# pca_mosfet_v3.net
KiCad netlist of a schematic drawn in EAGLE
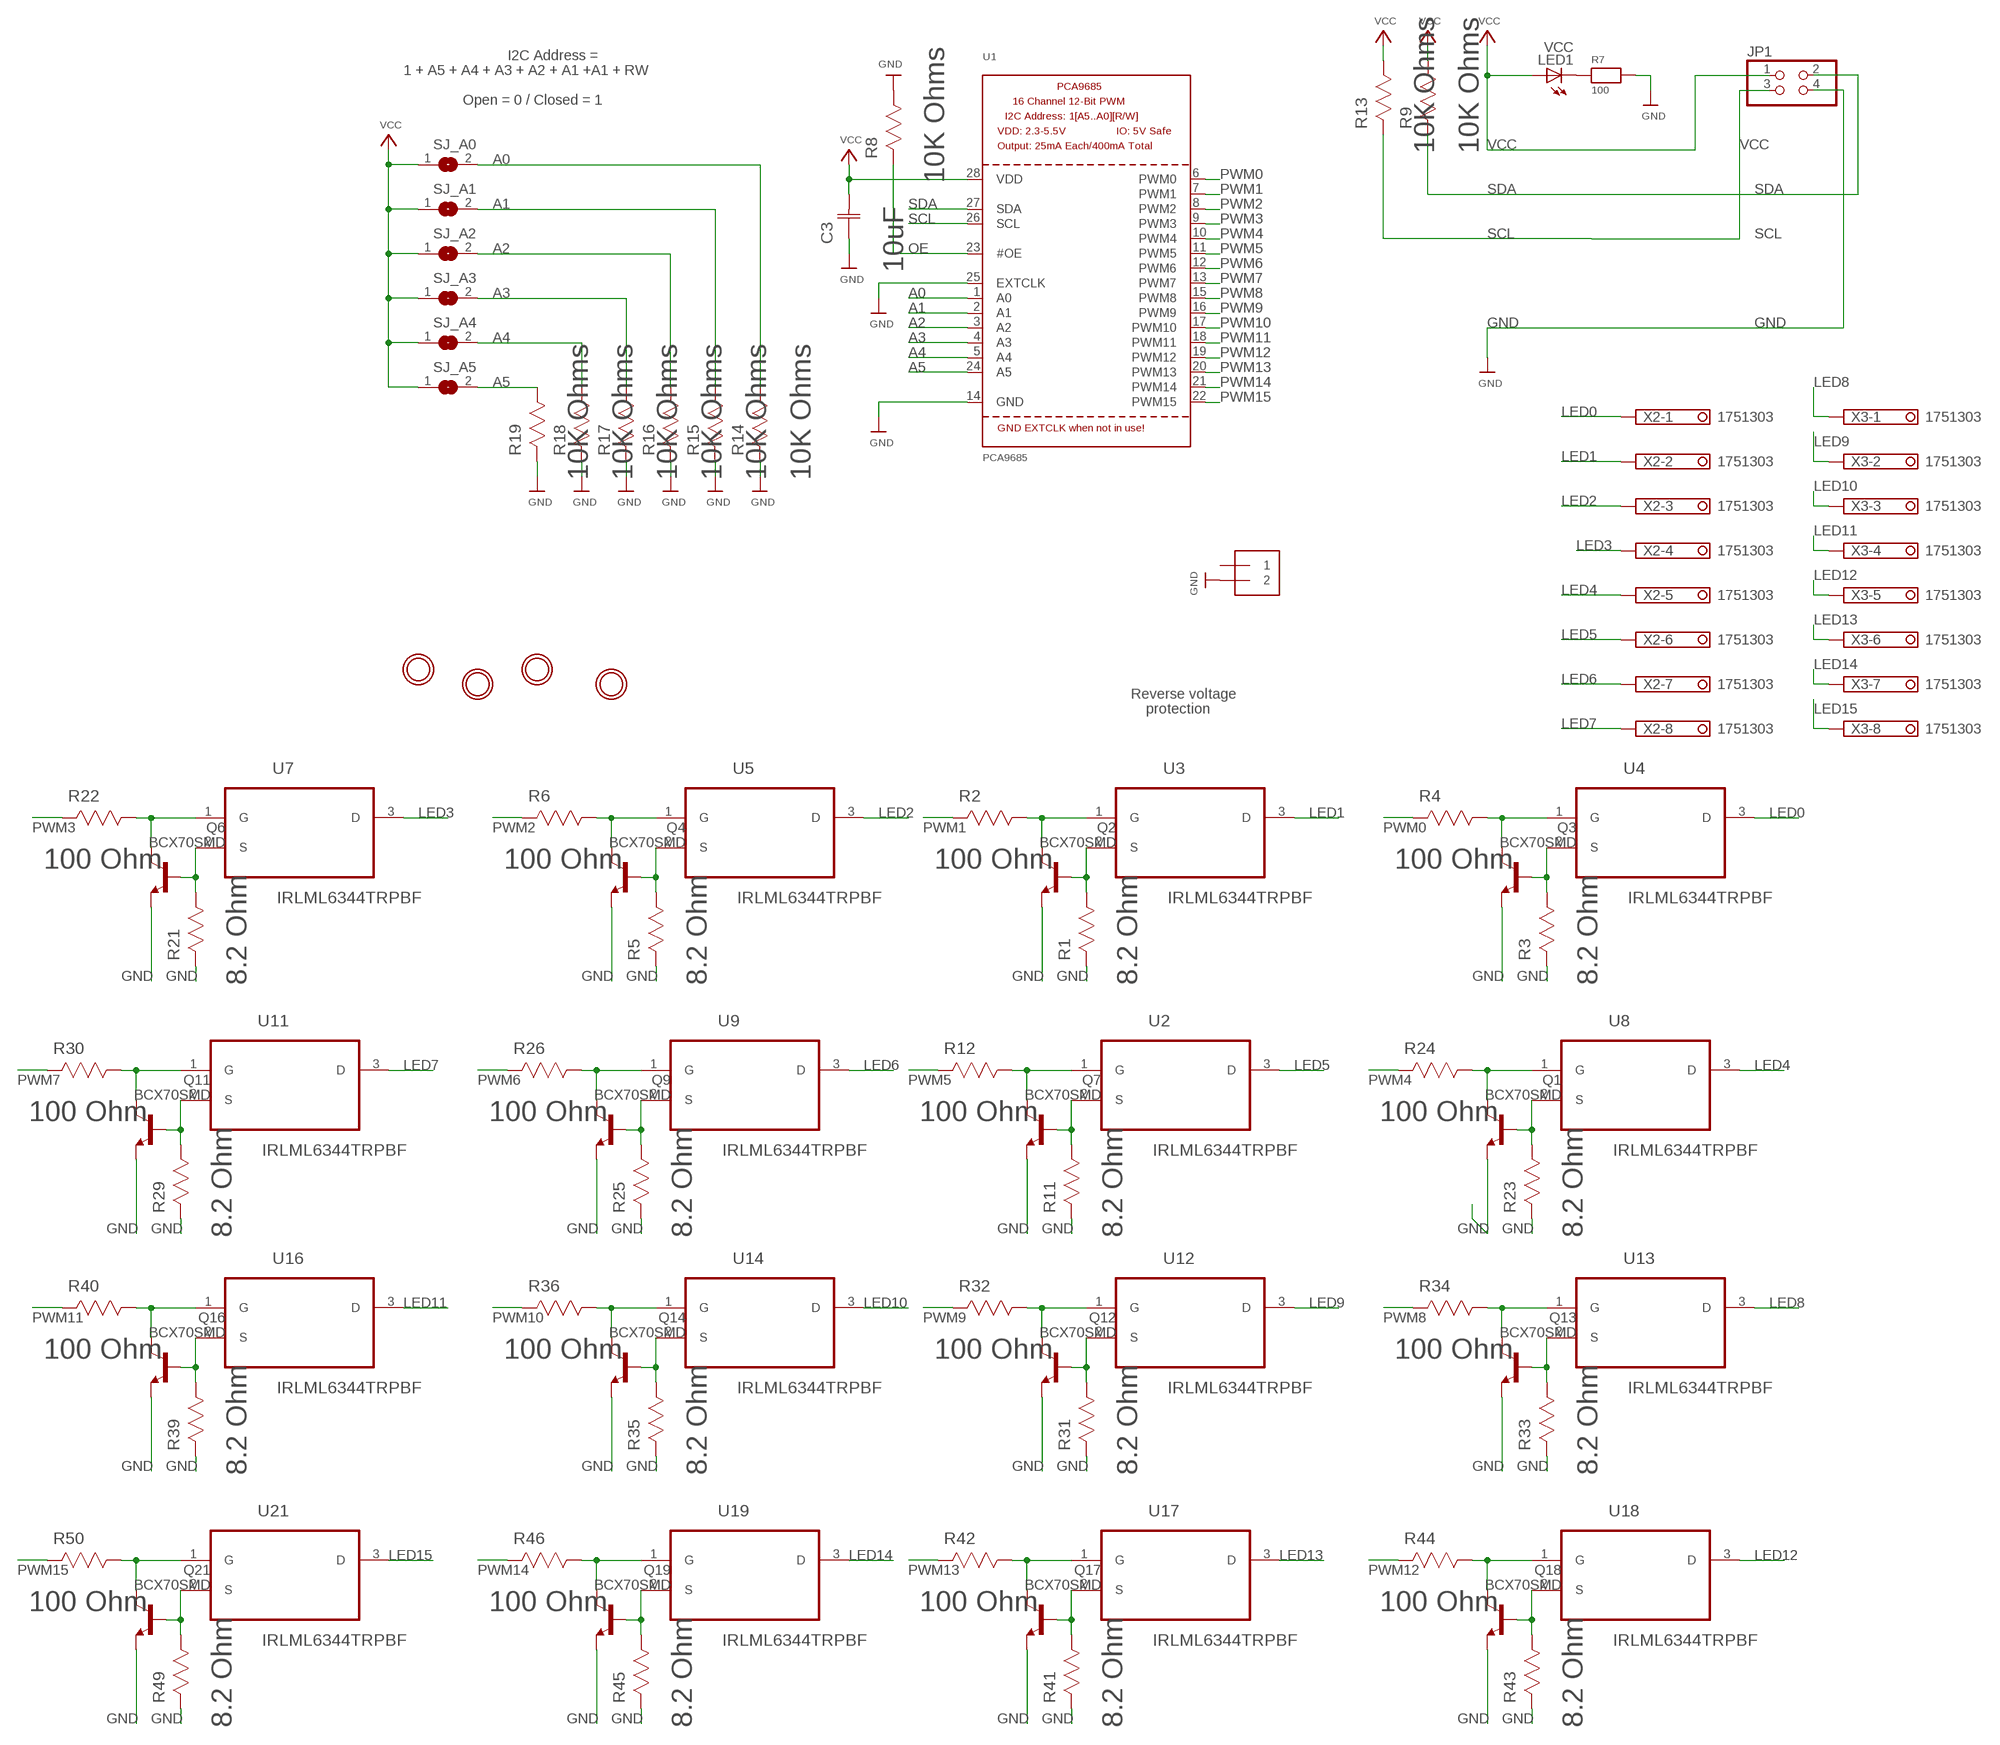
[diagram p0: schematic, sheet 1]

(export (version "E")
  (design (tool "Eeschema 10.0.6"))
  (components
    (comp (ref "C3")
      (value "10uF")
      (footprint "eagle-import:CAPC2013X145N")
      (fields (field (name "MPN") "CC0805KKX5R6BB106") (field (name "TOLERANCE") "±10%"))
      (libsource (lib "eagle-import") (part "CC0805KKX5R6BB106"))
    )
    (comp (ref "J1")
      (value "TERMBLOCK_1X2-3.5MM")
      (footprint "eagle-import:1X2-3.5MM")
      (libsource (lib "eagle-import") (part "TERMBLOCK_1X2-3.5MM"))
    )
    (comp (ref "JP1")
      (value "PINHD-2X02_MICROMATCH")
      (footprint "eagle-import:MICROMATCH-4")
      (libsource (lib "eagle-import") (part "PINHD-2X02_MICROMATCH"))
    )
    (comp (ref "LED1")
      (value "VCC")
      (footprint "eagle-import:SMARTLED-TTW")
      (libsource (lib "eagle-import") (part "LED"))
    )
    (comp (ref "Q1")
      (value "BCX70SMD")
      (footprint "eagle-import:SOT23")
      (libsource (lib "eagle-import") (part "BCX70SMD"))
    )
    (comp (ref "Q2")
      (value "BCX70SMD")
      (footprint "eagle-import:SOT23")
      (libsource (lib "eagle-import") (part "BCX70SMD"))
    )
    (comp (ref "Q3")
      (value "BCX70SMD")
      (footprint "eagle-import:SOT23")
      (libsource (lib "eagle-import") (part "BCX70SMD"))
    )
    (comp (ref "Q4")
      (value "BCX70SMD")
      (footprint "eagle-import:SOT23")
      (libsource (lib "eagle-import") (part "BCX70SMD"))
    )
    (comp (ref "Q6")
      (value "BCX70SMD")
      (footprint "eagle-import:SOT23")
      (libsource (lib "eagle-import") (part "BCX70SMD"))
    )
    (comp (ref "Q7")
      (value "BCX70SMD")
      (footprint "eagle-import:SOT23")
      (libsource (lib "eagle-import") (part "BCX70SMD"))
    )
    (comp (ref "Q9")
      (value "BCX70SMD")
      (footprint "eagle-import:SOT23")
      (libsource (lib "eagle-import") (part "BCX70SMD"))
    )
    (comp (ref "Q11")
      (value "BCX70SMD")
      (footprint "eagle-import:SOT23")
      (libsource (lib "eagle-import") (part "BCX70SMD"))
    )
    (comp (ref "Q12")
      (value "BCX70SMD")
      (footprint "eagle-import:SOT23")
      (libsource (lib "eagle-import") (part "BCX70SMD"))
    )
    (comp (ref "Q13")
      (value "BCX70SMD")
      (footprint "eagle-import:SOT23")
      (libsource (lib "eagle-import") (part "BCX70SMD"))
    )
    (comp (ref "Q14")
      (value "BCX70SMD")
      (footprint "eagle-import:SOT23")
      (libsource (lib "eagle-import") (part "BCX70SMD"))
    )
    (comp (ref "Q16")
      (value "BCX70SMD")
      (footprint "eagle-import:SOT23")
      (libsource (lib "eagle-import") (part "BCX70SMD"))
    )
    (comp (ref "Q17")
      (value "BCX70SMD")
      (footprint "eagle-import:SOT23")
      (libsource (lib "eagle-import") (part "BCX70SMD"))
    )
    (comp (ref "Q18")
      (value "BCX70SMD")
      (footprint "eagle-import:SOT23")
      (libsource (lib "eagle-import") (part "BCX70SMD"))
    )
    (comp (ref "Q19")
      (value "BCX70SMD")
      (footprint "eagle-import:SOT23")
      (libsource (lib "eagle-import") (part "BCX70SMD"))
    )
    (comp (ref "Q21")
      (value "BCX70SMD")
      (footprint "eagle-import:SOT23")
      (libsource (lib "eagle-import") (part "BCX70SMD"))
    )
    (comp (ref "R1")
      (value "8.2 Ohm")
      (footprint "eagle-import:RESC3225X71N")
      (fields (field (name "MPN") "ERJ-P14J8R2U") (field (name "TOLERANCE") "± 1 %"))
      (libsource (lib "eagle-import") (part "ERJ-P14J8R2U"))
    )
    (comp (ref "R2")
      (value "100 Ohm")
      (footprint "eagle-import:RESC3216X71N")
      (fields (field (name "MPN") "RC1206FR-07100RL") (field (name "TOLERANCE") "±1%"))
      (libsource (lib "eagle-import") (part "RC1206FR-07100RL"))
    )
    (comp (ref "R3")
      (value "8.2 Ohm")
      (footprint "eagle-import:RESC3225X71N")
      (fields (field (name "MPN") "ERJ-P14J8R2U") (field (name "TOLERANCE") "± 1 %"))
      (libsource (lib "eagle-import") (part "ERJ-P14J8R2U"))
    )
    (comp (ref "R4")
      (value "100 Ohm")
      (footprint "eagle-import:RESC3216X71N")
      (fields (field (name "MPN") "RC1206FR-07100RL") (field (name "TOLERANCE") "±1%"))
      (libsource (lib "eagle-import") (part "RC1206FR-07100RL"))
    )
    (comp (ref "R5")
      (value "8.2 Ohm")
      (footprint "eagle-import:RESC3225X71N")
      (fields (field (name "MPN") "ERJ-P14J8R2U") (field (name "TOLERANCE") "± 1 %"))
      (libsource (lib "eagle-import") (part "ERJ-P14J8R2U"))
    )
    (comp (ref "R6")
      (value "100 Ohm")
      (footprint "eagle-import:RESC3216X71N")
      (fields (field (name "MPN") "RC1206FR-07100RL") (field (name "TOLERANCE") "±1%"))
      (libsource (lib "eagle-import") (part "RC1206FR-07100RL"))
    )
    (comp (ref "R7")
      (value "100")
      (footprint "eagle-import:1206")
      (libsource (lib "eagle-import") (part "RESISTOR1206"))
    )
    (comp (ref "R8")
      (value "10K Ohms")
      (footprint "eagle-import:RESC3216X71N")
      (fields (field (name "MPN") "RC1206JR-0710KL") (field (name "TOLERANCE") "±5%"))
      (libsource (lib "eagle-import") (part "RC1206JR-0710KL"))
    )
    (comp (ref "R9")
      (value "10K Ohms")
      (footprint "eagle-import:RESC3216X71N")
      (fields (field (name "MPN") "RC1206JR-0710KL") (field (name "TOLERANCE") "±5%"))
      (libsource (lib "eagle-import") (part "RC1206JR-0710KL"))
    )
    (comp (ref "R11")
      (value "8.2 Ohm")
      (footprint "eagle-import:RESC3225X71N")
      (fields (field (name "MPN") "ERJ-P14J8R2U") (field (name "TOLERANCE") "± 1 %"))
      (libsource (lib "eagle-import") (part "ERJ-P14J8R2U"))
    )
    (comp (ref "R12")
      (value "100 Ohm")
      (footprint "eagle-import:RESC3216X71N")
      (fields (field (name "MPN") "RC1206FR-07100RL") (field (name "TOLERANCE") "±1%"))
      (libsource (lib "eagle-import") (part "RC1206FR-07100RL"))
    )
    (comp (ref "R13")
      (value "10K Ohms")
      (footprint "eagle-import:RESC3216X71N")
      (fields (field (name "MPN") "RC1206JR-0710KL") (field (name "TOLERANCE") "±5%"))
      (libsource (lib "eagle-import") (part "RC1206JR-0710KL"))
    )
    (comp (ref "R14")
      (value "10K Ohms")
      (footprint "eagle-import:RESC3216X71N")
      (fields (field (name "MPN") "RC1206JR-0710KL") (field (name "TOLERANCE") "±5%"))
      (libsource (lib "eagle-import") (part "RC1206JR-0710KL"))
    )
    (comp (ref "R15")
      (value "10K Ohms")
      (footprint "eagle-import:RESC3216X71N")
      (fields (field (name "MPN") "RC1206JR-0710KL") (field (name "TOLERANCE") "±5%"))
      (libsource (lib "eagle-import") (part "RC1206JR-0710KL"))
    )
    (comp (ref "R16")
      (value "10K Ohms")
      (footprint "eagle-import:RESC3216X71N")
      (fields (field (name "MPN") "RC1206JR-0710KL") (field (name "TOLERANCE") "±5%"))
      (libsource (lib "eagle-import") (part "RC1206JR-0710KL"))
    )
    (comp (ref "R17")
      (value "10K Ohms")
      (footprint "eagle-import:RESC3216X71N")
      (fields (field (name "MPN") "RC1206JR-0710KL") (field (name "TOLERANCE") "±5%"))
      (libsource (lib "eagle-import") (part "RC1206JR-0710KL"))
    )
    (comp (ref "R18")
      (value "10K Ohms")
      (footprint "eagle-import:RESC3216X71N")
      (fields (field (name "MPN") "RC1206JR-0710KL") (field (name "TOLERANCE") "±5%"))
      (libsource (lib "eagle-import") (part "RC1206JR-0710KL"))
    )
    (comp (ref "R19")
      (value "10K Ohms")
      (footprint "eagle-import:RESC3216X71N")
      (fields (field (name "MPN") "RC1206JR-0710KL") (field (name "TOLERANCE") "±5%"))
      (libsource (lib "eagle-import") (part "RC1206JR-0710KL"))
    )
    (comp (ref "R21")
      (value "8.2 Ohm")
      (footprint "eagle-import:RESC3225X71N")
      (fields (field (name "MPN") "ERJ-P14J8R2U") (field (name "TOLERANCE") "± 1 %"))
      (libsource (lib "eagle-import") (part "ERJ-P14J8R2U"))
    )
    (comp (ref "R22")
      (value "100 Ohm")
      (footprint "eagle-import:RESC3216X71N")
      (fields (field (name "MPN") "RC1206FR-07100RL") (field (name "TOLERANCE") "±1%"))
      (libsource (lib "eagle-import") (part "RC1206FR-07100RL"))
    )
    (comp (ref "R23")
      (value "8.2 Ohm")
      (footprint "eagle-import:RESC3225X71N")
      (fields (field (name "MPN") "ERJ-P14J8R2U") (field (name "TOLERANCE") "± 1 %"))
      (libsource (lib "eagle-import") (part "ERJ-P14J8R2U"))
    )
    (comp (ref "R24")
      (value "100 Ohm")
      (footprint "eagle-import:RESC3216X71N")
      (fields (field (name "MPN") "RC1206FR-07100RL") (field (name "TOLERANCE") "±1%"))
      (libsource (lib "eagle-import") (part "RC1206FR-07100RL"))
    )
    (comp (ref "R25")
      (value "8.2 Ohm")
      (footprint "eagle-import:RESC3225X71N")
      (fields (field (name "MPN") "ERJ-P14J8R2U") (field (name "TOLERANCE") "± 1 %"))
      (libsource (lib "eagle-import") (part "ERJ-P14J8R2U"))
    )
    (comp (ref "R26")
      (value "100 Ohm")
      (footprint "eagle-import:RESC3216X71N")
      (fields (field (name "MPN") "RC1206FR-07100RL") (field (name "TOLERANCE") "±1%"))
      (libsource (lib "eagle-import") (part "RC1206FR-07100RL"))
    )
    (comp (ref "R29")
      (value "8.2 Ohm")
      (footprint "eagle-import:RESC3225X71N")
      (fields (field (name "MPN") "ERJ-P14J8R2U") (field (name "TOLERANCE") "± 1 %"))
      (libsource (lib "eagle-import") (part "ERJ-P14J8R2U"))
    )
    (comp (ref "R30")
      (value "100 Ohm")
      (footprint "eagle-import:RESC3216X71N")
      (fields (field (name "MPN") "RC1206FR-07100RL") (field (name "TOLERANCE") "±1%"))
      (libsource (lib "eagle-import") (part "RC1206FR-07100RL"))
    )
    (comp (ref "R31")
      (value "8.2 Ohm")
      (footprint "eagle-import:RESC3225X71N")
      (fields (field (name "MPN") "ERJ-P14J8R2U") (field (name "TOLERANCE") "± 1 %"))
      (libsource (lib "eagle-import") (part "ERJ-P14J8R2U"))
    )
    (comp (ref "R32")
      (value "100 Ohm")
      (footprint "eagle-import:RESC3216X71N")
      (fields (field (name "MPN") "RC1206FR-07100RL") (field (name "TOLERANCE") "±1%"))
      (libsource (lib "eagle-import") (part "RC1206FR-07100RL"))
    )
    (comp (ref "R33")
      (value "8.2 Ohm")
      (footprint "eagle-import:RESC3225X71N")
      (fields (field (name "MPN") "ERJ-P14J8R2U") (field (name "TOLERANCE") "± 1 %"))
      (libsource (lib "eagle-import") (part "ERJ-P14J8R2U"))
    )
    (comp (ref "R34")
      (value "100 Ohm")
      (footprint "eagle-import:RESC3216X71N")
      (fields (field (name "MPN") "RC1206FR-07100RL") (field (name "TOLERANCE") "±1%"))
      (libsource (lib "eagle-import") (part "RC1206FR-07100RL"))
    )
    (comp (ref "R35")
      (value "8.2 Ohm")
      (footprint "eagle-import:RESC3225X71N")
      (fields (field (name "MPN") "ERJ-P14J8R2U") (field (name "TOLERANCE") "± 1 %"))
      (libsource (lib "eagle-import") (part "ERJ-P14J8R2U"))
    )
    (comp (ref "R36")
      (value "100 Ohm")
      (footprint "eagle-import:RESC3216X71N")
      (fields (field (name "MPN") "RC1206FR-07100RL") (field (name "TOLERANCE") "±1%"))
      (libsource (lib "eagle-import") (part "RC1206FR-07100RL"))
    )
    (comp (ref "R39")
      (value "8.2 Ohm")
      (footprint "eagle-import:RESC3225X71N")
      (fields (field (name "MPN") "ERJ-P14J8R2U") (field (name "TOLERANCE") "± 1 %"))
      (libsource (lib "eagle-import") (part "ERJ-P14J8R2U"))
    )
    (comp (ref "R40")
      (value "100 Ohm")
      (footprint "eagle-import:RESC3216X71N")
      (fields (field (name "MPN") "RC1206FR-07100RL") (field (name "TOLERANCE") "±1%"))
      (libsource (lib "eagle-import") (part "RC1206FR-07100RL"))
    )
    (comp (ref "R41")
      (value "8.2 Ohm")
      (footprint "eagle-import:RESC3225X71N")
      (fields (field (name "MPN") "ERJ-P14J8R2U") (field (name "TOLERANCE") "± 1 %"))
      (libsource (lib "eagle-import") (part "ERJ-P14J8R2U"))
    )
    (comp (ref "R42")
      (value "100 Ohm")
      (footprint "eagle-import:RESC3216X71N")
      (fields (field (name "MPN") "RC1206FR-07100RL") (field (name "TOLERANCE") "±1%"))
      (libsource (lib "eagle-import") (part "RC1206FR-07100RL"))
    )
    (comp (ref "R43")
      (value "8.2 Ohm")
      (footprint "eagle-import:RESC3225X71N")
      (fields (field (name "MPN") "ERJ-P14J8R2U") (field (name "TOLERANCE") "± 1 %"))
      (libsource (lib "eagle-import") (part "ERJ-P14J8R2U"))
    )
    (comp (ref "R44")
      (value "100 Ohm")
      (footprint "eagle-import:RESC3216X71N")
      (fields (field (name "MPN") "RC1206FR-07100RL") (field (name "TOLERANCE") "±1%"))
      (libsource (lib "eagle-import") (part "RC1206FR-07100RL"))
    )
    (comp (ref "R45")
      (value "8.2 Ohm")
      (footprint "eagle-import:RESC3225X71N")
      (fields (field (name "MPN") "ERJ-P14J8R2U") (field (name "TOLERANCE") "± 1 %"))
      (libsource (lib "eagle-import") (part "ERJ-P14J8R2U"))
    )
    (comp (ref "R46")
      (value "100 Ohm")
      (footprint "eagle-import:RESC3216X71N")
      (fields (field (name "MPN") "RC1206FR-07100RL") (field (name "TOLERANCE") "±1%"))
      (libsource (lib "eagle-import") (part "RC1206FR-07100RL"))
    )
    (comp (ref "R49")
      (value "8.2 Ohm")
      (footprint "eagle-import:RESC3225X71N")
      (fields (field (name "MPN") "ERJ-P14J8R2U") (field (name "TOLERANCE") "± 1 %"))
      (libsource (lib "eagle-import") (part "ERJ-P14J8R2U"))
    )
    (comp (ref "R50")
      (value "100 Ohm")
      (footprint "eagle-import:RESC3216X71N")
      (fields (field (name "MPN") "RC1206FR-07100RL") (field (name "TOLERANCE") "±1%"))
      (libsource (lib "eagle-import") (part "RC1206FR-07100RL"))
    )
    (comp (ref "SJ_A0")
      (value "SOLDERJUMPERREFLOW_NOPASTE")
      (footprint "eagle-import:SOLDERJUMPER_REFLOW_NOPASTE")
      (libsource (lib "eagle-import") (part "SOLDERJUMPERREFLOW_NOPASTE"))
    )
    (comp (ref "SJ_A1")
      (value "SOLDERJUMPERREFLOW_NOPASTE")
      (footprint "eagle-import:SOLDERJUMPER_REFLOW_NOPASTE")
      (libsource (lib "eagle-import") (part "SOLDERJUMPERREFLOW_NOPASTE"))
    )
    (comp (ref "SJ_A2")
      (value "SOLDERJUMPERREFLOW_NOPASTE")
      (footprint "eagle-import:SOLDERJUMPER_REFLOW_NOPASTE")
      (libsource (lib "eagle-import") (part "SOLDERJUMPERREFLOW_NOPASTE"))
    )
    (comp (ref "SJ_A3")
      (value "SOLDERJUMPERREFLOW_NOPASTE")
      (footprint "eagle-import:SOLDERJUMPER_REFLOW_NOPASTE")
      (libsource (lib "eagle-import") (part "SOLDERJUMPERREFLOW_NOPASTE"))
    )
    (comp (ref "SJ_A4")
      (value "SOLDERJUMPERREFLOW_NOPASTE")
      (footprint "eagle-import:SOLDERJUMPER_REFLOW_NOPASTE")
      (libsource (lib "eagle-import") (part "SOLDERJUMPERREFLOW_NOPASTE"))
    )
    (comp (ref "SJ_A5")
      (value "SOLDERJUMPERREFLOW_NOPASTE")
      (footprint "eagle-import:SOLDERJUMPER_REFLOW_NOPASTE")
      (libsource (lib "eagle-import") (part "SOLDERJUMPERREFLOW_NOPASTE"))
    )
    (comp (ref "U$1")
      (value "MOUNTINGHOLE2.5")
      (footprint "eagle-import:MOUNTINGHOLE_2.5_PLATED")
      (libsource (lib "eagle-import") (part "MOUNTINGHOLE2.5"))
    )
    (comp (ref "U$2")
      (value "MOUNTINGHOLE2.5")
      (footprint "eagle-import:MOUNTINGHOLE_2.5_PLATED")
      (libsource (lib "eagle-import") (part "MOUNTINGHOLE2.5"))
    )
    (comp (ref "U$3")
      (value "MOUNTINGHOLE2.5")
      (footprint "eagle-import:MOUNTINGHOLE_2.5_PLATED")
      (libsource (lib "eagle-import") (part "MOUNTINGHOLE2.5"))
    )
    (comp (ref "U$48")
      (value "MOUNTINGHOLE2.5")
      (footprint "eagle-import:MOUNTINGHOLE_2.5_PLATED")
      (libsource (lib "eagle-import") (part "MOUNTINGHOLE2.5"))
    )
    (comp (ref "U1")
      (value "PCA9685")
      (footprint "eagle-import:TSSOP28")
      (libsource (lib "eagle-import") (part "PCA9685"))
    )
    (comp (ref "U2")
      (value "IRLML6344TRPBF")
      (footprint "eagle-import:SOT95P240X112-3N")
      (libsource (lib "eagle-import") (part "IRLML6344TRPBF"))
    )
    (comp (ref "U3")
      (value "IRLML6344TRPBF")
      (footprint "eagle-import:SOT95P240X112-3N")
      (libsource (lib "eagle-import") (part "IRLML6344TRPBF"))
    )
    (comp (ref "U4")
      (value "IRLML6344TRPBF")
      (footprint "eagle-import:SOT95P240X112-3N")
      (libsource (lib "eagle-import") (part "IRLML6344TRPBF"))
    )
    (comp (ref "U5")
      (value "IRLML6344TRPBF")
      (footprint "eagle-import:SOT95P240X112-3N")
      (libsource (lib "eagle-import") (part "IRLML6344TRPBF"))
    )
    (comp (ref "U7")
      (value "IRLML6344TRPBF")
      (footprint "eagle-import:SOT95P240X112-3N")
      (libsource (lib "eagle-import") (part "IRLML6344TRPBF"))
    )
    (comp (ref "U8")
      (value "IRLML6344TRPBF")
      (footprint "eagle-import:SOT95P240X112-3N")
      (libsource (lib "eagle-import") (part "IRLML6344TRPBF"))
    )
    (comp (ref "U9")
      (value "IRLML6344TRPBF")
      (footprint "eagle-import:SOT95P240X112-3N")
      (libsource (lib "eagle-import") (part "IRLML6344TRPBF"))
    )
    (comp (ref "U11")
      (value "IRLML6344TRPBF")
      (footprint "eagle-import:SOT95P240X112-3N")
      (libsource (lib "eagle-import") (part "IRLML6344TRPBF"))
    )
    (comp (ref "U12")
      (value "IRLML6344TRPBF")
      (footprint "eagle-import:SOT95P240X112-3N")
      (libsource (lib "eagle-import") (part "IRLML6344TRPBF"))
    )
    (comp (ref "U13")
      (value "IRLML6344TRPBF")
      (footprint "eagle-import:SOT95P240X112-3N")
      (libsource (lib "eagle-import") (part "IRLML6344TRPBF"))
    )
    (comp (ref "U14")
      (value "IRLML6344TRPBF")
      (footprint "eagle-import:SOT95P240X112-3N")
      (libsource (lib "eagle-import") (part "IRLML6344TRPBF"))
    )
    (comp (ref "U16")
      (value "IRLML6344TRPBF")
      (footprint "eagle-import:SOT95P240X112-3N")
      (libsource (lib "eagle-import") (part "IRLML6344TRPBF"))
    )
    (comp (ref "U17")
      (value "IRLML6344TRPBF")
      (footprint "eagle-import:SOT95P240X112-3N")
      (libsource (lib "eagle-import") (part "IRLML6344TRPBF"))
    )
    (comp (ref "U18")
      (value "IRLML6344TRPBF")
      (footprint "eagle-import:SOT95P240X112-3N")
      (libsource (lib "eagle-import") (part "IRLML6344TRPBF"))
    )
    (comp (ref "U19")
      (value "IRLML6344TRPBF")
      (footprint "eagle-import:SOT95P240X112-3N")
      (libsource (lib "eagle-import") (part "IRLML6344TRPBF"))
    )
    (comp (ref "U21")
      (value "IRLML6344TRPBF")
      (footprint "eagle-import:SOT95P240X112-3N")
      (libsource (lib "eagle-import") (part "IRLML6344TRPBF"))
    )
    (comp (ref "X2")
      (value "1751303")
      (footprint "eagle-import:1751303")
      (libsource (lib "eagle-import") (part "1751303"))
    )
    (comp (ref "X3")
      (value "1751303")
      (footprint "eagle-import:1751303")
      (libsource (lib "eagle-import") (part "1751303"))
    )
  )
  (nets
    (net (code "1") (name "/A0") (class "Default")
      (node (ref "R14") (pin "1") (pinfunction "R1_1") (pintype "passive"))
      (node (ref "SJ_A0") (pin "2") (pinfunction "2_2") (pintype "passive"))
      (node (ref "U1") (pin "1") (pinfunction "A0_1") (pintype "bidirectional"))
    )
    (net (code "2") (name "/A1") (class "Default")
      (node (ref "R15") (pin "1") (pinfunction "R1_1") (pintype "passive"))
      (node (ref "SJ_A1") (pin "2") (pinfunction "2_2") (pintype "passive"))
      (node (ref "U1") (pin "2") (pinfunction "A1_2") (pintype "bidirectional"))
    )
    (net (code "3") (name "/A2") (class "Default")
      (node (ref "R16") (pin "1") (pinfunction "R1_1") (pintype "passive"))
      (node (ref "SJ_A2") (pin "2") (pinfunction "2_2") (pintype "passive"))
      (node (ref "U1") (pin "3") (pinfunction "A2_3") (pintype "bidirectional"))
    )
    (net (code "4") (name "/A3") (class "Default")
      (node (ref "R17") (pin "1") (pinfunction "R1_1") (pintype "passive"))
      (node (ref "SJ_A3") (pin "2") (pinfunction "2_2") (pintype "passive"))
      (node (ref "U1") (pin "4") (pinfunction "A3_4") (pintype "bidirectional"))
    )
    (net (code "5") (name "/A4") (class "Default")
      (node (ref "R18") (pin "1") (pinfunction "R1_1") (pintype "passive"))
      (node (ref "SJ_A4") (pin "2") (pinfunction "2_2") (pintype "passive"))
      (node (ref "U1") (pin "5") (pinfunction "A4_5") (pintype "bidirectional"))
    )
    (net (code "6") (name "/A5") (class "Default")
      (node (ref "R19") (pin "1") (pinfunction "R1_1") (pintype "passive"))
      (node (ref "SJ_A5") (pin "2") (pinfunction "2_2") (pintype "passive"))
      (node (ref "U1") (pin "24") (pinfunction "A5_24") (pintype "bidirectional"))
    )
    (net (code "7") (name "/LED0") (class "Default")
      (node (ref "U4") (pin "3") (pinfunction "D_3") (pintype "output"))
      (node (ref "X2") (pin "1") (pinfunction "K_1") (pintype "passive"))
    )
    (net (code "8") (name "/LED1") (class "Default")
      (node (ref "U3") (pin "3") (pinfunction "D_3") (pintype "output"))
      (node (ref "X2") (pin "2") (pinfunction "K_2") (pintype "passive"))
    )
    (net (code "9") (name "/LED2") (class "Default")
      (node (ref "U5") (pin "3") (pinfunction "D_3") (pintype "output"))
      (node (ref "X2") (pin "3") (pinfunction "K_3") (pintype "passive"))
    )
    (net (code "10") (name "/LED3") (class "Default")
      (node (ref "U7") (pin "3") (pinfunction "D_3") (pintype "output"))
      (node (ref "X2") (pin "4") (pinfunction "K_4") (pintype "passive"))
    )
    (net (code "11") (name "/LED4") (class "Default")
      (node (ref "U8") (pin "3") (pinfunction "D_3") (pintype "output"))
      (node (ref "X2") (pin "5") (pinfunction "K_5") (pintype "passive"))
    )
    (net (code "12") (name "/LED5") (class "Default")
      (node (ref "U2") (pin "3") (pinfunction "D_3") (pintype "output"))
      (node (ref "X2") (pin "6") (pinfunction "K_6") (pintype "passive"))
    )
    (net (code "13") (name "/LED6") (class "Default")
      (node (ref "U9") (pin "3") (pinfunction "D_3") (pintype "output"))
      (node (ref "X2") (pin "7") (pinfunction "K_7") (pintype "passive"))
    )
    (net (code "14") (name "/LED7") (class "Default")
      (node (ref "U11") (pin "3") (pinfunction "D_3") (pintype "output"))
      (node (ref "X2") (pin "8") (pinfunction "K_8") (pintype "passive"))
    )
    (net (code "15") (name "/LED8") (class "Default")
      (node (ref "U13") (pin "3") (pinfunction "D_3") (pintype "output"))
      (node (ref "X3") (pin "1") (pinfunction "K_1") (pintype "passive"))
    )
    (net (code "16") (name "/LED9") (class "Default")
      (node (ref "U12") (pin "3") (pinfunction "D_3") (pintype "output"))
      (node (ref "X3") (pin "2") (pinfunction "K_2") (pintype "passive"))
    )
    (net (code "17") (name "/LED10") (class "Default")
      (node (ref "U14") (pin "3") (pinfunction "D_3") (pintype "output"))
      (node (ref "X3") (pin "3") (pinfunction "K_3") (pintype "passive"))
    )
    (net (code "18") (name "/LED11") (class "Default")
      (node (ref "U16") (pin "3") (pinfunction "D_3") (pintype "output"))
      (node (ref "X3") (pin "4") (pinfunction "K_4") (pintype "passive"))
    )
    (net (code "19") (name "/LED12") (class "Default")
      (node (ref "U18") (pin "3") (pinfunction "D_3") (pintype "output"))
      (node (ref "X3") (pin "5") (pinfunction "K_5") (pintype "passive"))
    )
    (net (code "20") (name "/LED13") (class "Default")
      (node (ref "U17") (pin "3") (pinfunction "D_3") (pintype "output"))
      (node (ref "X3") (pin "6") (pinfunction "K_6") (pintype "passive"))
    )
    (net (code "21") (name "/LED14") (class "Default")
      (node (ref "U19") (pin "3") (pinfunction "D_3") (pintype "output"))
      (node (ref "X3") (pin "7") (pinfunction "K_7") (pintype "passive"))
    )
    (net (code "22") (name "/LED15") (class "Default")
      (node (ref "U21") (pin "3") (pinfunction "D_3") (pintype "output"))
      (node (ref "X3") (pin "8") (pinfunction "K_8") (pintype "passive"))
    )
    (net (code "23") (name "/OE") (class "Default")
      (node (ref "R8") (pin "2") (pinfunction "R2_2") (pintype "passive"))
      (node (ref "U1") (pin "23") (pinfunction "#OE_23") (pintype "input"))
    )
    (net (code "24") (name "/PWM0") (class "Default")
      (node (ref "R4") (pin "2") (pinfunction "R2_2") (pintype "passive"))
      (node (ref "U1") (pin "6") (pinfunction "PWM0_6") (pintype "output"))
    )
    (net (code "25") (name "/PWM1") (class "Default")
      (node (ref "R2") (pin "2") (pinfunction "R2_2") (pintype "passive"))
      (node (ref "U1") (pin "7") (pinfunction "PWM1_7") (pintype "output"))
    )
    (net (code "26") (name "/PWM2") (class "Default")
      (node (ref "R6") (pin "2") (pinfunction "R2_2") (pintype "passive"))
      (node (ref "U1") (pin "8") (pinfunction "PWM2_8") (pintype "output"))
    )
    (net (code "27") (name "/PWM3") (class "Default")
      (node (ref "R22") (pin "2") (pinfunction "R2_2") (pintype "passive"))
      (node (ref "U1") (pin "9") (pinfunction "PWM3_9") (pintype "output"))
    )
    (net (code "28") (name "/PWM4") (class "Default")
      (node (ref "R24") (pin "2") (pinfunction "R2_2") (pintype "passive"))
      (node (ref "U1") (pin "10") (pinfunction "PWM4_10") (pintype "output"))
    )
    (net (code "29") (name "/PWM5") (class "Default")
      (node (ref "R12") (pin "2") (pinfunction "R2_2") (pintype "passive"))
      (node (ref "U1") (pin "11") (pinfunction "PWM5_11") (pintype "output"))
    )
    (net (code "30") (name "/PWM6") (class "Default")
      (node (ref "R26") (pin "2") (pinfunction "R2_2") (pintype "passive"))
      (node (ref "U1") (pin "12") (pinfunction "PWM6_12") (pintype "output"))
    )
    (net (code "31") (name "/PWM7") (class "Default")
      (node (ref "R30") (pin "2") (pinfunction "R2_2") (pintype "passive"))
      (node (ref "U1") (pin "13") (pinfunction "PWM7_13") (pintype "output"))
    )
    (net (code "32") (name "/PWM8") (class "Default")
      (node (ref "R34") (pin "2") (pinfunction "R2_2") (pintype "passive"))
      (node (ref "U1") (pin "15") (pinfunction "PWM8_15") (pintype "output"))
    )
    (net (code "33") (name "/PWM9") (class "Default")
      (node (ref "R32") (pin "2") (pinfunction "R2_2") (pintype "passive"))
      (node (ref "U1") (pin "16") (pinfunction "PWM9_16") (pintype "output"))
    )
    (net (code "34") (name "/PWM10") (class "Default")
      (node (ref "R36") (pin "2") (pinfunction "R2_2") (pintype "passive"))
      (node (ref "U1") (pin "17") (pinfunction "PWM10_17") (pintype "output"))
    )
    (net (code "35") (name "/PWM11") (class "Default")
      (node (ref "R40") (pin "2") (pinfunction "R2_2") (pintype "passive"))
      (node (ref "U1") (pin "18") (pinfunction "PWM11_18") (pintype "output"))
    )
    (net (code "36") (name "/PWM12") (class "Default")
      (node (ref "R44") (pin "2") (pinfunction "R2_2") (pintype "passive"))
      (node (ref "U1") (pin "19") (pinfunction "PWM12_19") (pintype "output"))
    )
    (net (code "37") (name "/PWM13") (class "Default")
      (node (ref "R42") (pin "2") (pinfunction "R2_2") (pintype "passive"))
      (node (ref "U1") (pin "20") (pinfunction "PWM13_20") (pintype "output"))
    )
    (net (code "38") (name "/PWM14") (class "Default")
      (node (ref "R46") (pin "2") (pinfunction "R2_2") (pintype "passive"))
      (node (ref "U1") (pin "21") (pinfunction "PWM14_21") (pintype "output"))
    )
    (net (code "39") (name "/PWM15") (class "Default")
      (node (ref "R50") (pin "2") (pinfunction "R2_2") (pintype "passive"))
      (node (ref "U1") (pin "22") (pinfunction "PWM15_22") (pintype "output"))
    )
    (net (code "40") (name "/SCL") (class "Default")
      (node (ref "JP1") (pin "3") (pinfunction "3_3") (pintype "passive"))
      (node (ref "R13") (pin "2") (pinfunction "R2_2") (pintype "passive"))
      (node (ref "U1") (pin "26") (pinfunction "SCL_26") (pintype "bidirectional"))
    )
    (net (code "41") (name "/SDA") (class "Default")
      (node (ref "JP1") (pin "2") (pinfunction "2_2") (pintype "passive"))
      (node (ref "R9") (pin "2") (pinfunction "R2_2") (pintype "passive"))
      (node (ref "U1") (pin "27") (pinfunction "SDA_27") (pintype "bidirectional"))
    )
    (net (code "42") (name "GND") (class "Default")
      (node (ref "C3") (pin "1") (pinfunction "C1_1") (pintype "passive"))
      (node (ref "J1") (pin "2") (pinfunction "2_2") (pintype "passive"))
      (node (ref "JP1") (pin "4") (pinfunction "4_4") (pintype "passive"))
      (node (ref "Q1") (pin "2") (pinfunction "E_2") (pintype "passive"))
      (node (ref "Q11") (pin "2") (pinfunction "E_2") (pintype "passive"))
      (node (ref "Q12") (pin "2") (pinfunction "E_2") (pintype "passive"))
      (node (ref "Q13") (pin "2") (pinfunction "E_2") (pintype "passive"))
      (node (ref "Q14") (pin "2") (pinfunction "E_2") (pintype "passive"))
      (node (ref "Q16") (pin "2") (pinfunction "E_2") (pintype "passive"))
      (node (ref "Q17") (pin "2") (pinfunction "E_2") (pintype "passive"))
      (node (ref "Q18") (pin "2") (pinfunction "E_2") (pintype "passive"))
      (node (ref "Q19") (pin "2") (pinfunction "E_2") (pintype "passive"))
      (node (ref "Q2") (pin "2") (pinfunction "E_2") (pintype "passive"))
      (node (ref "Q21") (pin "2") (pinfunction "E_2") (pintype "passive"))
      (node (ref "Q3") (pin "2") (pinfunction "E_2") (pintype "passive"))
      (node (ref "Q4") (pin "2") (pinfunction "E_2") (pintype "passive"))
      (node (ref "Q6") (pin "2") (pinfunction "E_2") (pintype "passive"))
      (node (ref "Q7") (pin "2") (pinfunction "E_2") (pintype "passive"))
      (node (ref "Q9") (pin "2") (pinfunction "E_2") (pintype "passive"))
      (node (ref "R1") (pin "2") (pinfunction "R2_2") (pintype "passive"))
      (node (ref "R11") (pin "2") (pinfunction "R2_2") (pintype "passive"))
      (node (ref "R14") (pin "2") (pinfunction "R2_2") (pintype "passive"))
      (node (ref "R15") (pin "2") (pinfunction "R2_2") (pintype "passive"))
      (node (ref "R16") (pin "2") (pinfunction "R2_2") (pintype "passive"))
      (node (ref "R17") (pin "2") (pinfunction "R2_2") (pintype "passive"))
      (node (ref "R18") (pin "2") (pinfunction "R2_2") (pintype "passive"))
      (node (ref "R19") (pin "2") (pinfunction "R2_2") (pintype "passive"))
      (node (ref "R21") (pin "2") (pinfunction "R2_2") (pintype "passive"))
      (node (ref "R23") (pin "2") (pinfunction "R2_2") (pintype "passive"))
      (node (ref "R25") (pin "2") (pinfunction "R2_2") (pintype "passive"))
      (node (ref "R29") (pin "2") (pinfunction "R2_2") (pintype "passive"))
      (node (ref "R3") (pin "2") (pinfunction "R2_2") (pintype "passive"))
      (node (ref "R31") (pin "2") (pinfunction "R2_2") (pintype "passive"))
      (node (ref "R33") (pin "2") (pinfunction "R2_2") (pintype "passive"))
      (node (ref "R35") (pin "2") (pinfunction "R2_2") (pintype "passive"))
      (node (ref "R39") (pin "2") (pinfunction "R2_2") (pintype "passive"))
      (node (ref "R41") (pin "2") (pinfunction "R2_2") (pintype "passive"))
      (node (ref "R43") (pin "2") (pinfunction "R2_2") (pintype "passive"))
      (node (ref "R45") (pin "2") (pinfunction "R2_2") (pintype "passive"))
      (node (ref "R49") (pin "2") (pinfunction "R2_2") (pintype "passive"))
      (node (ref "R5") (pin "2") (pinfunction "R2_2") (pintype "passive"))
      (node (ref "R7") (pin "2") (pinfunction "2_2") (pintype "passive"))
      (node (ref "R8") (pin "1") (pinfunction "R1_1") (pintype "passive"))
      (node (ref "U1") (pin "14") (pinfunction "GND_14") (pintype "power_in"))
      (node (ref "U1") (pin "25") (pinfunction "EXTCLK_25") (pintype "input"))
    )
    (net (code "43") (name "Net-(LED1-C)") (class "Default")
      (node (ref "LED1") (pin "C@1") (pinfunction "C_C@1") (pintype "passive"))
      (node (ref "R7") (pin "1") (pinfunction "1_1") (pintype "passive"))
    )
    (net (code "44") (name "Net-(Q1-B)") (class "Default")
      (node (ref "Q1") (pin "1") (pinfunction "B_1") (pintype "passive"))
      (node (ref "R23") (pin "1") (pinfunction "R1_1") (pintype "passive"))
      (node (ref "U8") (pin "2") (pinfunction "S_2") (pintype "passive"))
    )
    (net (code "45") (name "Net-(Q1-C)") (class "Default")
      (node (ref "Q1") (pin "3") (pinfunction "C_3") (pintype "passive"))
      (node (ref "R24") (pin "1") (pinfunction "R1_1") (pintype "passive"))
      (node (ref "U8") (pin "1") (pinfunction "G_1") (pintype "input"))
    )
    (net (code "46") (name "Net-(Q2-B)") (class "Default")
      (node (ref "Q2") (pin "1") (pinfunction "B_1") (pintype "passive"))
      (node (ref "R1") (pin "1") (pinfunction "R1_1") (pintype "passive"))
      (node (ref "U3") (pin "2") (pinfunction "S_2") (pintype "passive"))
    )
    (net (code "47") (name "Net-(Q2-C)") (class "Default")
      (node (ref "Q2") (pin "3") (pinfunction "C_3") (pintype "passive"))
      (node (ref "R2") (pin "1") (pinfunction "R1_1") (pintype "passive"))
      (node (ref "U3") (pin "1") (pinfunction "G_1") (pintype "input"))
    )
    (net (code "48") (name "Net-(Q3-B)") (class "Default")
      (node (ref "Q3") (pin "1") (pinfunction "B_1") (pintype "passive"))
      (node (ref "R3") (pin "1") (pinfunction "R1_1") (pintype "passive"))
      (node (ref "U4") (pin "2") (pinfunction "S_2") (pintype "passive"))
    )
    (net (code "49") (name "Net-(Q3-C)") (class "Default")
      (node (ref "Q3") (pin "3") (pinfunction "C_3") (pintype "passive"))
      (node (ref "R4") (pin "1") (pinfunction "R1_1") (pintype "passive"))
      (node (ref "U4") (pin "1") (pinfunction "G_1") (pintype "input"))
    )
    (net (code "50") (name "Net-(Q4-B)") (class "Default")
      (node (ref "Q4") (pin "1") (pinfunction "B_1") (pintype "passive"))
      (node (ref "R5") (pin "1") (pinfunction "R1_1") (pintype "passive"))
      (node (ref "U5") (pin "2") (pinfunction "S_2") (pintype "passive"))
    )
    (net (code "51") (name "Net-(Q4-C)") (class "Default")
      (node (ref "Q4") (pin "3") (pinfunction "C_3") (pintype "passive"))
      (node (ref "R6") (pin "1") (pinfunction "R1_1") (pintype "passive"))
      (node (ref "U5") (pin "1") (pinfunction "G_1") (pintype "input"))
    )
    (net (code "52") (name "Net-(Q6-B)") (class "Default")
      (node (ref "Q6") (pin "1") (pinfunction "B_1") (pintype "passive"))
      (node (ref "R21") (pin "1") (pinfunction "R1_1") (pintype "passive"))
      (node (ref "U7") (pin "2") (pinfunction "S_2") (pintype "passive"))
    )
    (net (code "53") (name "Net-(Q6-C)") (class "Default")
      (node (ref "Q6") (pin "3") (pinfunction "C_3") (pintype "passive"))
      (node (ref "R22") (pin "1") (pinfunction "R1_1") (pintype "passive"))
      (node (ref "U7") (pin "1") (pinfunction "G_1") (pintype "input"))
    )
    (net (code "54") (name "Net-(Q7-B)") (class "Default")
      (node (ref "Q7") (pin "1") (pinfunction "B_1") (pintype "passive"))
      (node (ref "R11") (pin "1") (pinfunction "R1_1") (pintype "passive"))
      (node (ref "U2") (pin "2") (pinfunction "S_2") (pintype "passive"))
    )
    (net (code "55") (name "Net-(Q7-C)") (class "Default")
      (node (ref "Q7") (pin "3") (pinfunction "C_3") (pintype "passive"))
      (node (ref "R12") (pin "1") (pinfunction "R1_1") (pintype "passive"))
      (node (ref "U2") (pin "1") (pinfunction "G_1") (pintype "input"))
    )
    (net (code "56") (name "Net-(Q9-B)") (class "Default")
      (node (ref "Q9") (pin "1") (pinfunction "B_1") (pintype "passive"))
      (node (ref "R25") (pin "1") (pinfunction "R1_1") (pintype "passive"))
      (node (ref "U9") (pin "2") (pinfunction "S_2") (pintype "passive"))
    )
    (net (code "57") (name "Net-(Q9-C)") (class "Default")
      (node (ref "Q9") (pin "3") (pinfunction "C_3") (pintype "passive"))
      (node (ref "R26") (pin "1") (pinfunction "R1_1") (pintype "passive"))
      (node (ref "U9") (pin "1") (pinfunction "G_1") (pintype "input"))
    )
    (net (code "58") (name "Net-(Q11-B)") (class "Default")
      (node (ref "Q11") (pin "1") (pinfunction "B_1") (pintype "passive"))
      (node (ref "R29") (pin "1") (pinfunction "R1_1") (pintype "passive"))
      (node (ref "U11") (pin "2") (pinfunction "S_2") (pintype "passive"))
    )
    (net (code "59") (name "Net-(Q11-C)") (class "Default")
      (node (ref "Q11") (pin "3") (pinfunction "C_3") (pintype "passive"))
      (node (ref "R30") (pin "1") (pinfunction "R1_1") (pintype "passive"))
      (node (ref "U11") (pin "1") (pinfunction "G_1") (pintype "input"))
    )
    (net (code "60") (name "Net-(Q12-B)") (class "Default")
      (node (ref "Q12") (pin "1") (pinfunction "B_1") (pintype "passive"))
      (node (ref "R31") (pin "1") (pinfunction "R1_1") (pintype "passive"))
      (node (ref "U12") (pin "2") (pinfunction "S_2") (pintype "passive"))
    )
    (net (code "61") (name "Net-(Q12-C)") (class "Default")
      (node (ref "Q12") (pin "3") (pinfunction "C_3") (pintype "passive"))
      (node (ref "R32") (pin "1") (pinfunction "R1_1") (pintype "passive"))
      (node (ref "U12") (pin "1") (pinfunction "G_1") (pintype "input"))
    )
    (net (code "62") (name "Net-(Q13-B)") (class "Default")
      (node (ref "Q13") (pin "1") (pinfunction "B_1") (pintype "passive"))
      (node (ref "R33") (pin "1") (pinfunction "R1_1") (pintype "passive"))
      (node (ref "U13") (pin "2") (pinfunction "S_2") (pintype "passive"))
    )
    (net (code "63") (name "Net-(Q13-C)") (class "Default")
      (node (ref "Q13") (pin "3") (pinfunction "C_3") (pintype "passive"))
      (node (ref "R34") (pin "1") (pinfunction "R1_1") (pintype "passive"))
      (node (ref "U13") (pin "1") (pinfunction "G_1") (pintype "input"))
    )
    (net (code "64") (name "Net-(Q14-B)") (class "Default")
      (node (ref "Q14") (pin "1") (pinfunction "B_1") (pintype "passive"))
      (node (ref "R35") (pin "1") (pinfunction "R1_1") (pintype "passive"))
      (node (ref "U14") (pin "2") (pinfunction "S_2") (pintype "passive"))
    )
    (net (code "65") (name "Net-(Q14-C)") (class "Default")
      (node (ref "Q14") (pin "3") (pinfunction "C_3") (pintype "passive"))
      (node (ref "R36") (pin "1") (pinfunction "R1_1") (pintype "passive"))
      (node (ref "U14") (pin "1") (pinfunction "G_1") (pintype "input"))
    )
    (net (code "66") (name "Net-(Q16-B)") (class "Default")
      (node (ref "Q16") (pin "1") (pinfunction "B_1") (pintype "passive"))
      (node (ref "R39") (pin "1") (pinfunction "R1_1") (pintype "passive"))
      (node (ref "U16") (pin "2") (pinfunction "S_2") (pintype "passive"))
    )
    (net (code "67") (name "Net-(Q16-C)") (class "Default")
      (node (ref "Q16") (pin "3") (pinfunction "C_3") (pintype "passive"))
      (node (ref "R40") (pin "1") (pinfunction "R1_1") (pintype "passive"))
      (node (ref "U16") (pin "1") (pinfunction "G_1") (pintype "input"))
    )
    (net (code "68") (name "Net-(Q17-B)") (class "Default")
      (node (ref "Q17") (pin "1") (pinfunction "B_1") (pintype "passive"))
      (node (ref "R41") (pin "1") (pinfunction "R1_1") (pintype "passive"))
      (node (ref "U17") (pin "2") (pinfunction "S_2") (pintype "passive"))
    )
    (net (code "69") (name "Net-(Q17-C)") (class "Default")
      (node (ref "Q17") (pin "3") (pinfunction "C_3") (pintype "passive"))
      (node (ref "R42") (pin "1") (pinfunction "R1_1") (pintype "passive"))
      (node (ref "U17") (pin "1") (pinfunction "G_1") (pintype "input"))
    )
    (net (code "70") (name "Net-(Q18-B)") (class "Default")
      (node (ref "Q18") (pin "1") (pinfunction "B_1") (pintype "passive"))
      (node (ref "R43") (pin "1") (pinfunction "R1_1") (pintype "passive"))
      (node (ref "U18") (pin "2") (pinfunction "S_2") (pintype "passive"))
    )
    (net (code "71") (name "Net-(Q18-C)") (class "Default")
      (node (ref "Q18") (pin "3") (pinfunction "C_3") (pintype "passive"))
      (node (ref "R44") (pin "1") (pinfunction "R1_1") (pintype "passive"))
      (node (ref "U18") (pin "1") (pinfunction "G_1") (pintype "input"))
    )
    (net (code "72") (name "Net-(Q19-B)") (class "Default")
      (node (ref "Q19") (pin "1") (pinfunction "B_1") (pintype "passive"))
      (node (ref "R45") (pin "1") (pinfunction "R1_1") (pintype "passive"))
      (node (ref "U19") (pin "2") (pinfunction "S_2") (pintype "passive"))
    )
    (net (code "73") (name "Net-(Q19-C)") (class "Default")
      (node (ref "Q19") (pin "3") (pinfunction "C_3") (pintype "passive"))
      (node (ref "R46") (pin "1") (pinfunction "R1_1") (pintype "passive"))
      (node (ref "U19") (pin "1") (pinfunction "G_1") (pintype "input"))
    )
    (net (code "74") (name "Net-(Q21-B)") (class "Default")
      (node (ref "Q21") (pin "1") (pinfunction "B_1") (pintype "passive"))
      (node (ref "R49") (pin "1") (pinfunction "R1_1") (pintype "passive"))
      (node (ref "U21") (pin "2") (pinfunction "S_2") (pintype "passive"))
    )
    (net (code "75") (name "Net-(Q21-C)") (class "Default")
      (node (ref "Q21") (pin "3") (pinfunction "C_3") (pintype "passive"))
      (node (ref "R50") (pin "1") (pinfunction "R1_1") (pintype "passive"))
      (node (ref "U21") (pin "1") (pinfunction "G_1") (pintype "input"))
    )
    (net (code "76") (name "VCC") (class "Default")
      (node (ref "C3") (pin "2") (pinfunction "C2_2") (pintype "passive"))
      (node (ref "JP1") (pin "1") (pinfunction "1_1") (pintype "passive"))
      (node (ref "LED1") (pin "A@1") (pinfunction "A_A@1") (pintype "passive"))
      (node (ref "R13") (pin "1") (pinfunction "R1_1") (pintype "passive"))
      (node (ref "R9") (pin "1") (pinfunction "R1_1") (pintype "passive"))
      (node (ref "SJ_A0") (pin "1") (pinfunction "1_1") (pintype "passive"))
      (node (ref "SJ_A1") (pin "1") (pinfunction "1_1") (pintype "passive"))
      (node (ref "SJ_A2") (pin "1") (pinfunction "1_1") (pintype "passive"))
      (node (ref "SJ_A3") (pin "1") (pinfunction "1_1") (pintype "passive"))
      (node (ref "SJ_A4") (pin "1") (pinfunction "1_1") (pintype "passive"))
      (node (ref "SJ_A5") (pin "1") (pinfunction "1_1") (pintype "passive"))
      (node (ref "U1") (pin "28") (pinfunction "VDD_28") (pintype "power_in"))
    )
    (net (code "77") (name "unconnected-(J1-Pad1)") (class "Default")
      (node (ref "J1") (pin "1") (pinfunction "1_1") (pintype "passive"))
    )
  )
)
